# PIC32MK.net
KiCad netlist of a schematic drawn in Altium Designer
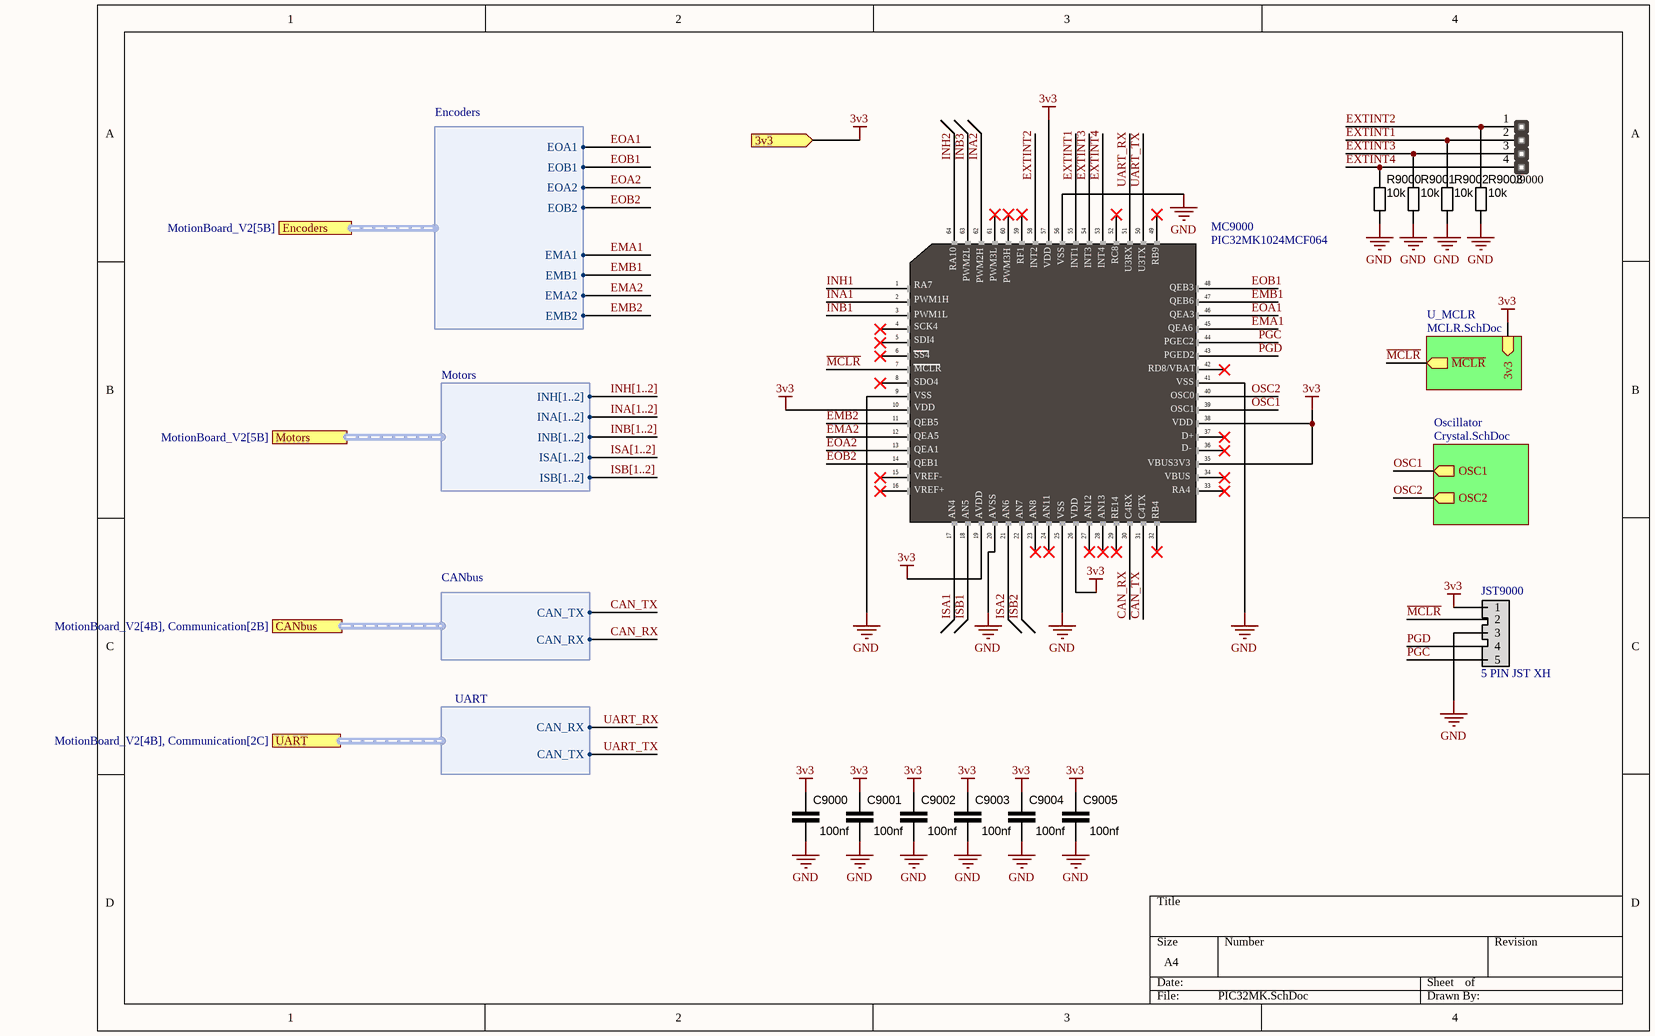
[diagram p0: PIC32MK.SchDoc]

(export (version "E")
  (design (tool "Eeschema 10.0.6"))
  (components
    (comp (ref "C9000")
      (value "100nf")
      (footprint "CAP_0603")
      (description "CAP CER 100nF 0603 25V X7R")
      (libsource (lib "CapacitorsIntegrated") (part "C000007"))
    )
    (comp (ref "C9001")
      (value "100nf")
      (footprint "CAP_0603")
      (description "CAP CER 100nF 0603 25V X7R")
      (libsource (lib "CapacitorsIntegrated") (part "C000007"))
    )
    (comp (ref "C9002")
      (value "100nf")
      (footprint "CAP_0603")
      (description "CAP CER 100nF 0603 25V X7R")
      (libsource (lib "CapacitorsIntegrated") (part "C000007"))
    )
    (comp (ref "C9003")
      (value "100nf")
      (footprint "CAP_0603")
      (description "CAP CER 100nF 0603 25V X7R")
      (libsource (lib "CapacitorsIntegrated") (part "C000007"))
    )
    (comp (ref "C9004")
      (value "100nf")
      (footprint "CAP_0603")
      (description "CAP CER 100nF 0603 25V X7R")
      (libsource (lib "CapacitorsIntegrated") (part "C000007"))
    )
    (comp (ref "C9005")
      (value "100nf")
      (footprint "CAP_0603")
      (description "CAP CER 100nF 0603 25V X7R")
      (libsource (lib "CapacitorsIntegrated") (part "C000007"))
    )
    (comp (ref "J9000")
      (value "EXTINT")
      (footprint "HM1X4")
      (libsource (lib "motion_board") (part "HEADER_1x4_1"))
    )
    (comp (ref "JST9000")
      (value "5 PIN JST XH")
      (footprint "Connectors:JST5PIN")
      (description "5 PIN JST XH 2.5mm pitch")
      (libsource (lib "Connectors") (part "JST5PIN"))
    )
    (comp (ref "MC9000")
      (value "PIC32MK1024MCF064")
      (footprint "MicroControllers:PIC32MK_64-TQFP")
      (description "PIC32 Motor Control Microcontroller\r\nPIC32MK1024MCF064\r\nPIC32MK1024MCM064\r\nCompatible")
      (libsource (lib "MicroControllers") (part "PIC32MK"))
    )
    (comp (ref "R9000")
      (value "10k")
      (footprint "RES_0603")
      (description "RES 10K OHM 1% 1/10W 0603")
      (libsource (lib "ResistorsIntegrated") (part "R000001"))
    )
    (comp (ref "R9001")
      (value "10k")
      (footprint "RES_0603")
      (description "RES 10K OHM 1% 1/10W 0603")
      (libsource (lib "ResistorsIntegrated") (part "R000001"))
    )
    (comp (ref "R9002")
      (value "10k")
      (footprint "RES_0603")
      (description "RES 10K OHM 1% 1/10W 0603")
      (libsource (lib "ResistorsIntegrated") (part "R000001"))
    )
    (comp (ref "R9003")
      (value "10k")
      (footprint "RES_0603")
      (description "RES 10K OHM 1% 1/10W 0603")
      (libsource (lib "ResistorsIntegrated") (part "R000001"))
    )
  )
  (nets
    (net (code "6") (name "/CAN_RX") (class "Default")
      (node (ref "MC9000") (pin "30") (pinfunction "30_30") (pintype "passive"))
    )
    (net (code "7") (name "/CAN_TX") (class "Default")
      (node (ref "MC9000") (pin "31") (pinfunction "31_31") (pintype "passive"))
    )
    (net (code "8") (name "/EMA1") (class "Default")
      (node (ref "MC9000") (pin "45") (pinfunction "45_45") (pintype "passive"))
    )
    (net (code "9") (name "/EMA2") (class "Default")
      (node (ref "MC9000") (pin "12") (pinfunction "12_12") (pintype "passive"))
    )
    (net (code "10") (name "/EMB1") (class "Default")
      (node (ref "MC9000") (pin "47") (pinfunction "47_47") (pintype "passive"))
    )
    (net (code "11") (name "/EMB2") (class "Default")
      (node (ref "MC9000") (pin "11") (pinfunction "11_11") (pintype "passive"))
    )
    (net (code "12") (name "/EOA1") (class "Default")
      (node (ref "MC9000") (pin "46") (pinfunction "46_46") (pintype "passive"))
    )
    (net (code "13") (name "/EOA2") (class "Default")
      (node (ref "MC9000") (pin "13") (pinfunction "13_13") (pintype "passive"))
    )
    (net (code "14") (name "/EOB1") (class "Default")
      (node (ref "MC9000") (pin "48") (pinfunction "48_48") (pintype "passive"))
    )
    (net (code "15") (name "/EOB2") (class "Default")
      (node (ref "MC9000") (pin "14") (pinfunction "14_14") (pintype "passive"))
    )
    (net (code "16") (name "/EXTINT1") (class "Default")
      (node (ref "J9000") (pin "2") (pinfunction "1_2") (pintype "passive"))
      (node (ref "MC9000") (pin "55") (pinfunction "55_55") (pintype "passive"))
      (node (ref "R9002") (pin "2") (pinfunction "2_2") (pintype "passive"))
    )
    (net (code "17") (name "/EXTINT2") (class "Default")
      (node (ref "J9000") (pin "1") (pinfunction "1_1") (pintype "passive"))
      (node (ref "MC9000") (pin "58") (pinfunction "58_58") (pintype "passive"))
      (node (ref "R9003") (pin "2") (pinfunction "2_2") (pintype "passive"))
    )
    (net (code "18") (name "/EXTINT3") (class "Default")
      (node (ref "J9000") (pin "3") (pinfunction "1_3") (pintype "passive"))
      (node (ref "MC9000") (pin "54") (pinfunction "54_54") (pintype "passive"))
      (node (ref "R9001") (pin "2") (pinfunction "2_2") (pintype "passive"))
    )
    (net (code "19") (name "/EXTINT4") (class "Default")
      (node (ref "J9000") (pin "4") (pinfunction "4_4") (pintype "passive"))
      (node (ref "MC9000") (pin "53") (pinfunction "53_53") (pintype "passive"))
      (node (ref "R9000") (pin "2") (pinfunction "2_2") (pintype "passive"))
    )
    (net (code "20") (name "/INA1") (class "Default")
      (node (ref "MC9000") (pin "2") (pinfunction "2_2") (pintype "passive"))
    )
    (net (code "21") (name "/INA2") (class "Default")
      (node (ref "MC9000") (pin "62") (pinfunction "62_62") (pintype "passive"))
    )
    (net (code "23") (name "/INB1") (class "Default")
      (node (ref "MC9000") (pin "3") (pinfunction "3_3") (pintype "passive"))
    )
    (net (code "24") (name "/INB3") (class "Default")
      (node (ref "MC9000") (pin "63") (pinfunction "63_63") (pintype "passive"))
    )
    (net (code "26") (name "/INH1") (class "Default")
      (node (ref "MC9000") (pin "1") (pinfunction "1_1") (pintype "passive"))
    )
    (net (code "27") (name "/INH2") (class "Default")
      (node (ref "MC9000") (pin "64") (pinfunction "64_64") (pintype "passive"))
    )
    (net (code "29") (name "/ISA1") (class "Default")
      (node (ref "MC9000") (pin "17") (pinfunction "17_17") (pintype "passive"))
    )
    (net (code "30") (name "/ISA2") (class "Default")
      (node (ref "MC9000") (pin "21") (pinfunction "21_21") (pintype "passive"))
    )
    (net (code "32") (name "/ISB1") (class "Default")
      (node (ref "MC9000") (pin "18") (pinfunction "18_18") (pintype "passive"))
    )
    (net (code "33") (name "/ISB2") (class "Default")
      (node (ref "MC9000") (pin "22") (pinfunction "22_22") (pintype "passive"))
    )
    (net (code "35") (name "/OSC1") (class "Default")
      (node (ref "MC9000") (pin "39") (pinfunction "39_39") (pintype "passive"))
    )
    (net (code "36") (name "/OSC2") (class "Default")
      (node (ref "MC9000") (pin "40") (pinfunction "40_40") (pintype "passive"))
    )
    (net (code "37") (name "/PGC") (class "Default")
      (node (ref "JST9000") (pin "5") (pinfunction "5_5") (pintype "passive"))
      (node (ref "MC9000") (pin "44") (pinfunction "44_44") (pintype "passive"))
    )
    (net (code "38") (name "/PGD") (class "Default")
      (node (ref "JST9000") (pin "4") (pinfunction "4_4") (pintype "passive"))
      (node (ref "MC9000") (pin "43") (pinfunction "43_43") (pintype "passive"))
    )
    (net (code "39") (name "/UART_RX") (class "Default")
      (node (ref "MC9000") (pin "51") (pinfunction "51_51") (pintype "passive"))
    )
    (net (code "40") (name "/UART_TX") (class "Default")
      (node (ref "MC9000") (pin "50") (pinfunction "50_50") (pintype "passive"))
    )
    (net (code "45") (name "/~{MCLR}") (class "Default")
      (node (ref "JST9000") (pin "2") (pinfunction "2_2") (pintype "passive"))
      (node (ref "MC9000") (pin "7") (pinfunction "7_7") (pintype "passive"))
    )
    (net (code "46") (name "3v3") (class "Default")
      (node (ref "C9000") (pin "2") (pinfunction "2_2") (pintype "passive"))
      (node (ref "C9001") (pin "2") (pinfunction "2_2") (pintype "passive"))
      (node (ref "C9002") (pin "2") (pinfunction "2_2") (pintype "passive"))
      (node (ref "C9003") (pin "2") (pinfunction "2_2") (pintype "passive"))
      (node (ref "C9004") (pin "2") (pinfunction "2_2") (pintype "passive"))
      (node (ref "C9005") (pin "2") (pinfunction "2_2") (pintype "passive"))
      (node (ref "JST9000") (pin "1") (pinfunction "1_1") (pintype "passive"))
      (node (ref "MC9000") (pin "10") (pinfunction "10_10") (pintype "passive"))
      (node (ref "MC9000") (pin "19") (pinfunction "19_19") (pintype "passive"))
      (node (ref "MC9000") (pin "26") (pinfunction "26_26") (pintype "passive"))
      (node (ref "MC9000") (pin "35") (pinfunction "35_35") (pintype "passive"))
      (node (ref "MC9000") (pin "38") (pinfunction "38_38") (pintype "passive"))
      (node (ref "MC9000") (pin "57") (pinfunction "57_57") (pintype "passive"))
    )
    (net (code "47") (name "GND") (class "Default")
      (node (ref "C9000") (pin "1") (pinfunction "1_1") (pintype "passive"))
      (node (ref "C9001") (pin "1") (pinfunction "1_1") (pintype "passive"))
      (node (ref "C9002") (pin "1") (pinfunction "1_1") (pintype "passive"))
      (node (ref "C9003") (pin "1") (pinfunction "1_1") (pintype "passive"))
      (node (ref "C9004") (pin "1") (pinfunction "1_1") (pintype "passive"))
      (node (ref "C9005") (pin "1") (pinfunction "1_1") (pintype "passive"))
      (node (ref "JST9000") (pin "3") (pinfunction "3_3") (pintype "passive"))
      (node (ref "MC9000") (pin "20") (pinfunction "20_20") (pintype "passive"))
      (node (ref "MC9000") (pin "25") (pinfunction "25_25") (pintype "passive"))
      (node (ref "MC9000") (pin "41") (pinfunction "41_41") (pintype "passive"))
      (node (ref "MC9000") (pin "56") (pinfunction "56_56") (pintype "passive"))
      (node (ref "MC9000") (pin "9") (pinfunction "9_9") (pintype "passive"))
      (node (ref "R9000") (pin "1") (pinfunction "1_1") (pintype "passive"))
      (node (ref "R9001") (pin "1") (pinfunction "1_1") (pintype "passive"))
      (node (ref "R9002") (pin "1") (pinfunction "1_1") (pintype "passive"))
      (node (ref "R9003") (pin "1") (pinfunction "1_1") (pintype "passive"))
    )
    (net (code "48") (name "unconnected-(MC9000-Pad4)") (class "Default")
      (node (ref "MC9000") (pin "4") (pinfunction "4_4") (pintype "passive+no_connect"))
    )
    (net (code "49") (name "unconnected-(MC9000-Pad5)") (class "Default")
      (node (ref "MC9000") (pin "5") (pinfunction "5_5") (pintype "passive+no_connect"))
    )
    (net (code "50") (name "unconnected-(MC9000-Pad6)") (class "Default")
      (node (ref "MC9000") (pin "6") (pinfunction "6_6") (pintype "passive+no_connect"))
    )
    (net (code "51") (name "unconnected-(MC9000-Pad8)") (class "Default")
      (node (ref "MC9000") (pin "8") (pinfunction "8_8") (pintype "passive+no_connect"))
    )
    (net (code "52") (name "unconnected-(MC9000-Pad15)") (class "Default")
      (node (ref "MC9000") (pin "15") (pinfunction "15_15") (pintype "passive+no_connect"))
    )
    (net (code "53") (name "unconnected-(MC9000-Pad16)") (class "Default")
      (node (ref "MC9000") (pin "16") (pinfunction "16_16") (pintype "passive+no_connect"))
    )
    (net (code "54") (name "unconnected-(MC9000-Pad23)") (class "Default")
      (node (ref "MC9000") (pin "23") (pinfunction "23_23") (pintype "passive+no_connect"))
    )
    (net (code "55") (name "unconnected-(MC9000-Pad24)") (class "Default")
      (node (ref "MC9000") (pin "24") (pinfunction "24_24") (pintype "passive+no_connect"))
    )
    (net (code "56") (name "unconnected-(MC9000-Pad27)") (class "Default")
      (node (ref "MC9000") (pin "27") (pinfunction "27_27") (pintype "passive+no_connect"))
    )
    (net (code "57") (name "unconnected-(MC9000-Pad28)") (class "Default")
      (node (ref "MC9000") (pin "28") (pinfunction "28_28") (pintype "passive+no_connect"))
    )
    (net (code "58") (name "unconnected-(MC9000-Pad29)") (class "Default")
      (node (ref "MC9000") (pin "29") (pinfunction "29_29") (pintype "passive+no_connect"))
    )
    (net (code "59") (name "unconnected-(MC9000-Pad32)") (class "Default")
      (node (ref "MC9000") (pin "32") (pinfunction "32_32") (pintype "passive+no_connect"))
    )
    (net (code "60") (name "unconnected-(MC9000-Pad33)") (class "Default")
      (node (ref "MC9000") (pin "33") (pinfunction "33_33") (pintype "passive+no_connect"))
    )
    (net (code "61") (name "unconnected-(MC9000-Pad34)") (class "Default")
      (node (ref "MC9000") (pin "34") (pinfunction "34_34") (pintype "passive+no_connect"))
    )
    (net (code "62") (name "unconnected-(MC9000-Pad36)") (class "Default")
      (node (ref "MC9000") (pin "36") (pinfunction "36_36") (pintype "passive+no_connect"))
    )
    (net (code "63") (name "unconnected-(MC9000-Pad37)") (class "Default")
      (node (ref "MC9000") (pin "37") (pinfunction "37_37") (pintype "passive+no_connect"))
    )
    (net (code "64") (name "unconnected-(MC9000-Pad42)") (class "Default")
      (node (ref "MC9000") (pin "42") (pinfunction "42_42") (pintype "passive+no_connect"))
    )
    (net (code "65") (name "unconnected-(MC9000-Pad49)") (class "Default")
      (node (ref "MC9000") (pin "49") (pinfunction "49_49") (pintype "passive+no_connect"))
    )
    (net (code "66") (name "unconnected-(MC9000-Pad52)") (class "Default")
      (node (ref "MC9000") (pin "52") (pinfunction "52_52") (pintype "passive+no_connect"))
    )
    (net (code "67") (name "unconnected-(MC9000-Pad59)") (class "Default")
      (node (ref "MC9000") (pin "59") (pinfunction "59_59") (pintype "passive+no_connect"))
    )
    (net (code "68") (name "unconnected-(MC9000-Pad60)") (class "Default")
      (node (ref "MC9000") (pin "60") (pinfunction "60_60") (pintype "passive+no_connect"))
    )
    (net (code "69") (name "unconnected-(MC9000-Pad61)") (class "Default")
      (node (ref "MC9000") (pin "61") (pinfunction "61_61") (pintype "passive+no_connect"))
    )
  )
)
